# PowerSupply.net
KiCad netlist of a schematic drawn in Altium Designer
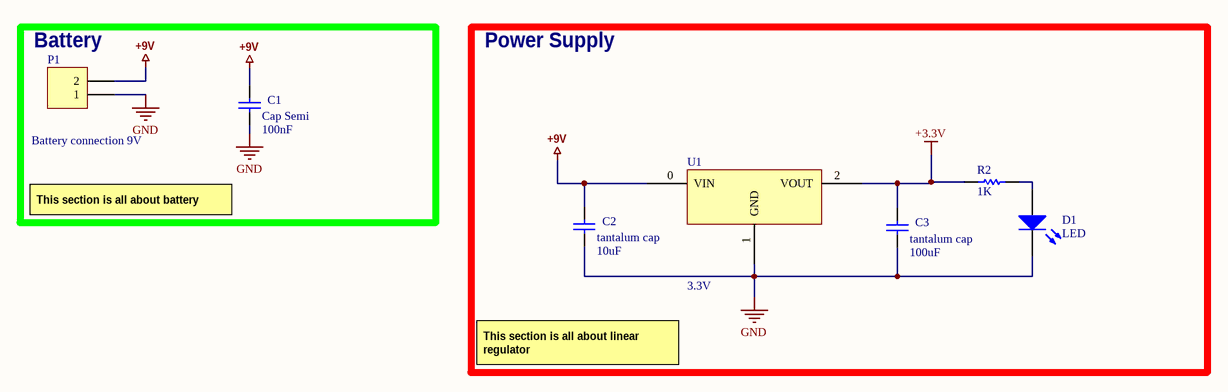
[diagram p0: PowerSupply.SchDoc]

(export (version "E")
  (design (tool "Eeschema 10.0.6"))
  (components
    (comp (ref "C1")
      (value "Cap Semi")
      (footprint "C1206")
      (description "Capacitor (Semiconductor SIM Model)")
      (fields (field (name "ALTIUM_VALUE") "100nF") (field (name "PUBLISHER") "Altium Limited"))
      (libsource (lib "Miscellaneous Devices") (part "Cap Semi"))
    )
    (comp (ref "C2")
      (value "tantalum cap")
      (footprint "C1206")
      (description "Capacitor (Semiconductor SIM Model)")
      (fields (field (name "ALTIUM_VALUE") "10uF") (field (name "PUBLISHER") "Altium Limited"))
      (libsource (lib "Miscellaneous Devices") (part "Cap Semi"))
    )
    (comp (ref "C3")
      (value "tantalum cap")
      (footprint "C1206")
      (description "Capacitor (Semiconductor SIM Model)")
      (fields (field (name "ALTIUM_VALUE") "100uF") (field (name "PUBLISHER") "Altium Limited"))
      (libsource (lib "Miscellaneous Devices") (part "Cap Semi"))
    )
    (comp (ref "D1")
      (value "LED")
      (footprint "MY_LED_0805")
      (description "Typical INFRARED GaAs LED")
      (fields (field (name "ASID PART NUMBER") "LED-AS"))
      (libsource (lib "Mylib+Rev+4") (part "LED"))
    )
    (comp (ref "P1")
      (value "Battery connection 9V")
      (footprint "HDR1X2H")
      (description "Header, 2-Pin, Right Angle")
      (fields (field (name "VOLTAGE") "9V") (field (name "PUBLISHER") "Altium Limited"))
      (libsource (lib "Miscellaneous Connectors") (part "Header 2H"))
    )
    (comp (ref "R2")
      (value "1K")
      (footprint "MY_0805")
      (description "Standard resistor")
      (fields (field (name "ASID PART NUMBER") "Res-AS"))
      (libsource (lib "Mylib+Rev+4") (part "Res"))
    )
    (comp (ref "U1")
      (value "~")
      (footprint "4-Pin SOT")
      (description "The LM1117 is a low dropout voltage regulator with a\r\ndropout of 1.2 V at 800 mA of load current")
      (fields (field (name "OUTPUT VOLTAGE") "3.3V"))
      (libsource (lib "smartmcu") (part "LM1117"))
    )
  )
  (nets
    (net (code "1") (name "+3.3V") (class "Default")
      (node (ref "C3") (pin "2") (pinfunction "2_2") (pintype "passive"))
      (node (ref "R2") (pin "1") (pinfunction "1_1") (pintype "passive"))
      (node (ref "U1") (pin "2") (pinfunction "VOUT_2") (pintype "passive"))
    )
    (net (code "2") (name "+9V") (class "Default")
      (node (ref "C1") (pin "2") (pinfunction "2_2") (pintype "passive"))
      (node (ref "C2") (pin "2") (pinfunction "2_2") (pintype "passive"))
      (node (ref "P1") (pin "2") (pinfunction "2_2") (pintype "passive"))
      (node (ref "U1") (pin "0") (pinfunction "VIN_0") (pintype "passive"))
    )
    (net (code "3") (name "GND") (class "Default")
      (node (ref "C1") (pin "1") (pinfunction "1_1") (pintype "passive"))
      (node (ref "C2") (pin "1") (pinfunction "1_1") (pintype "passive"))
      (node (ref "C3") (pin "1") (pinfunction "1_1") (pintype "passive"))
      (node (ref "D1") (pin "K") (pinfunction "K_K") (pintype "passive"))
      (node (ref "P1") (pin "1") (pinfunction "1_1") (pintype "passive"))
      (node (ref "U1") (pin "1") (pinfunction "GND_1") (pintype "passive"))
    )
    (net (code "4") (name "Net-(D1-PadA)") (class "Default")
      (node (ref "D1") (pin "A") (pinfunction "A_A") (pintype "passive"))
      (node (ref "R2") (pin "2") (pinfunction "2_2") (pintype "passive"))
    )
  )
)
